# FT232B.net
KiCad netlist of a schematic drawn in Altium Designer
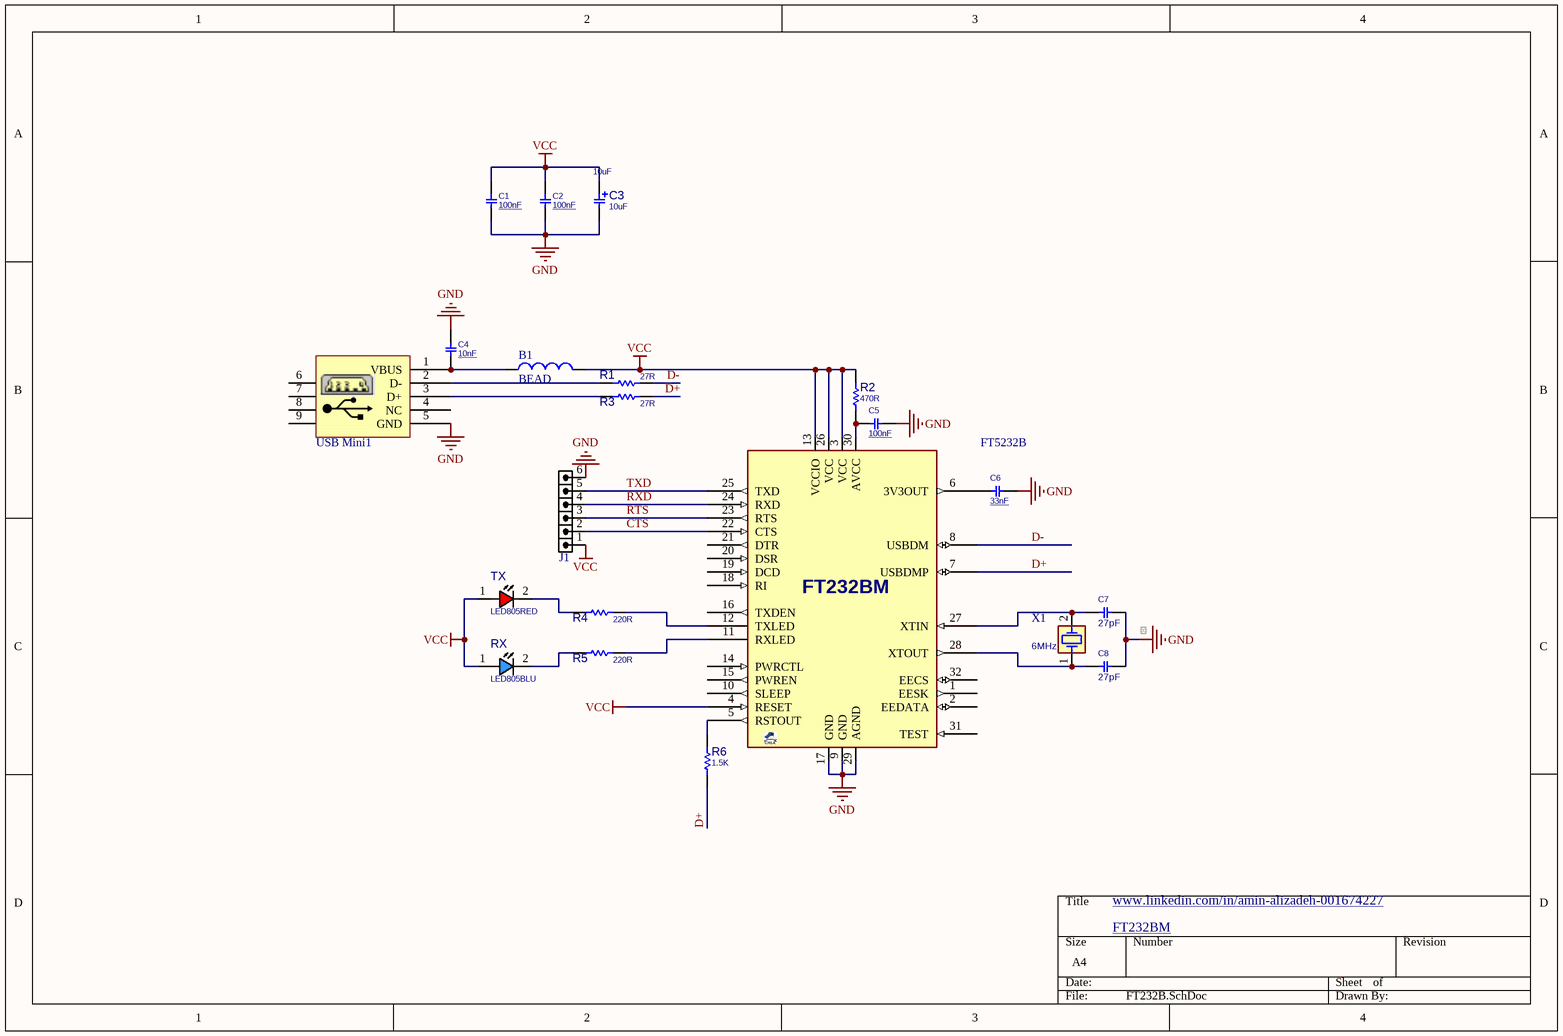
[diagram p0: FT232B.SchDoc]

(export (version "E")
  (design (tool "Eeschema 10.0.6"))
  (components
    (comp (ref "B1")
      (value "BEAD")
      (footprint "RES 0805 (2012X06L)")
      (description "FERIT BEAD SMD 1206")
      (libsource (lib "OMID_DXP_LIB93") (part "FERIT BEAD"))
    )
    (comp (ref "C1")
      (value "100nF")
      (footprint "C0805")
      (description "CAP, MLCC, -F, -V, MATERIAL, -%, 0201")
      (fields (field (name "MANF_P#") "MANF_PART#"))
      (libsource (lib "passive_smd") (part "CAP_SMD_MLCC_0805"))
    )
    (comp (ref "C2")
      (value "100nF")
      (footprint "C0805")
      (description "CAP, MLCC, -F, -V, MATERIAL, -%, 0201")
      (fields (field (name "MANF_P#") "MANF_PART#"))
      (libsource (lib "passive_smd") (part "CAP_SMD_MLCC_0805"))
    )
    (comp (ref "C3")
      (value "10uF")
      (footprint "C_EL_8")
      (description "CAP, THD, ELEC,")
      (fields
        (field (name "MANF_P#") "MANF_PART#")
        (field (name "MANF") "MANF")
        (field (name "ALTIUM_VALUE") "10uF")
      )
      (libsource (lib "passive_smd") (part "CAP_SMD_EL_8"))
    )
    (comp (ref "C4")
      (value "10nF")
      (footprint "C0805")
      (description "CAP, MLCC, -F, -V, MATERIAL, -%, 0201")
      (fields (field (name "MANF_P#") "MANF_PART#"))
      (libsource (lib "passive_smd") (part "CAP_SMD_MLCC_0805"))
    )
    (comp (ref "C5")
      (value "100nF")
      (footprint "C0805")
      (description "CAP, MLCC, -F, -V, MATERIAL, -%, 0201")
      (fields (field (name "MANF_P#") "MANF_PART#"))
      (libsource (lib "passive_smd") (part "CAP_SMD_MLCC_0805"))
    )
    (comp (ref "C6")
      (value "33nF")
      (footprint "C0805")
      (description "CAP, MLCC, -F, -V, MATERIAL, -%, 0201")
      (fields (field (name "MANF_P#") "MANF_PART#"))
      (libsource (lib "passive_smd") (part "CAP_SMD_MLCC_0805"))
    )
    (comp (ref "C7")
      (value "27pF")
      (footprint "C0805")
      (description "CAP, MLCC")
      (fields (field (name "MANF_P#") "MANF_PART#"))
      (libsource (lib "passive_smd") (part "CAP_SMD_MLCC_0805"))
    )
    (comp (ref "C8")
      (value "27pF")
      (footprint "C0805")
      (description "CAP, MLCC")
      (fields (field (name "MANF_P#") "MANF_PART#"))
      (libsource (lib "passive_smd") (part "CAP_SMD_MLCC_0805"))
    )
    (comp (ref "FT5232B")
      (value "FT232BM")
      (footprint "QFG80_32")
      (description "USB-UART")
      (fields (field (name "MANF") "FTDI"))
      (libsource (lib "usbic") (part "FT232BM_QFP32"))
    )
    (comp (ref "J1")
      (value "HDR1X6")
      (footprint "HDRR_M_1X6")
      (description "CONN, HEADER, Male, pitch: 2.54mm, 6POS")
      (libsource (lib "conn_header_2.54_ra") (part "HDRR_M_1X6"))
    )
    (comp (ref "R1")
      (value "27R")
      (footprint "R0805")
      (description "RESISTOR, SMD")
      (libsource (lib "passive_smd") (part "RES_SMD_0805"))
    )
    (comp (ref "R2")
      (value "470R")
      (footprint "R0805")
      (description "RESISTOR, SMD")
      (libsource (lib "passive_smd") (part "RES_SMD_0805"))
    )
    (comp (ref "R3")
      (value "27R")
      (footprint "R0805")
      (description "RESISTOR, SMD")
      (libsource (lib "passive_smd") (part "RES_SMD_0805"))
    )
    (comp (ref "R4")
      (value "220R")
      (footprint "R0805")
      (description "RESISTOR, SMD")
      (libsource (lib "passive_smd") (part "RES_SMD_0805"))
    )
    (comp (ref "R5")
      (value "220R")
      (footprint "R0805")
      (description "RESISTOR, SMD")
      (libsource (lib "passive_smd") (part "RES_SMD_0805"))
    )
    (comp (ref "R6")
      (value "1.5K")
      (footprint "R0805")
      (description "RESISTOR, SMD")
      (libsource (lib "passive_smd") (part "RES_SMD_0805"))
    )
    (comp (ref "RX")
      (value "LED805BLU")
      (footprint "LED0805BLU")
      (description "LED, SMD, 0805, BLUE")
      (fields (field (name "MANF") "MANF") (field (name "MANF_P#") "MANF_PART#"))
      (libsource (lib "led(diode)") (part "LED_SMD_0805_BLU"))
    )
    (comp (ref "TX")
      (value "LED805RED")
      (footprint "LED0805RED")
      (description "LED, SMD, 0805, RED")
      (fields (field (name "MANF") "MANF") (field (name "MANF_P#") "MANF_PART#"))
      (libsource (lib "led(diode)") (part "LED_SMD_0805_RED"))
    )
    (comp (ref "USB Mini1")
      (value "USB_Mini")
      (footprint "USB_Mini.2")
      (description "USB Mini")
      (fields (field (name "PUBLISHER") "Altium Limited"))
      (libsource (lib "A.Mohebbi") (part "USB_Mini"))
    )
    (comp (ref "X1")
      (value "6MHz")
      (footprint "XTL_2_11X5")
      (description "Crystal MOST POPULAR ABL HC49 PACKAGE")
      (fields (field (name "MANF") "ABRACON") (field (name "MANF_P#") "ABLS-8.000MHZ-B4-T"))
      (libsource (lib "crystal") (part "XTL_2_HC49_8MHz_SMD"))
    )
  )
  (nets
    (net (code "1") (name "/CTS") (class "Default")
      (node (ref "FT5232B") (pin "22") (pinfunction "CTS_22") (pintype "input"))
      (node (ref "J1") (pin "2") (pinfunction "2_2") (pintype "passive"))
    )
    (net (code "2") (name "/D+") (class "Default")
      (node (ref "FT5232B") (pin "7") (pinfunction "USBDMP_7") (pintype "bidirectional"))
      (node (ref "R3") (pin "1") (pinfunction "1_1") (pintype "passive"))
      (node (ref "R6") (pin "2") (pinfunction "2_2") (pintype "passive"))
    )
    (net (code "3") (name "/D-") (class "Default")
      (node (ref "FT5232B") (pin "8") (pinfunction "USBDM_8") (pintype "bidirectional"))
      (node (ref "R1") (pin "1") (pinfunction "1_1") (pintype "passive"))
    )
    (net (code "4") (name "/RTS") (class "Default")
      (node (ref "FT5232B") (pin "23") (pinfunction "RTS_23") (pintype "output"))
      (node (ref "J1") (pin "3") (pinfunction "3_3") (pintype "passive"))
    )
    (net (code "5") (name "/RXD") (class "Default")
      (node (ref "FT5232B") (pin "24") (pinfunction "RXD_24") (pintype "input"))
      (node (ref "J1") (pin "4") (pinfunction "4_4") (pintype "passive"))
    )
    (net (code "6") (name "/TXD") (class "Default")
      (node (ref "FT5232B") (pin "25") (pinfunction "TXD_25") (pintype "output"))
      (node (ref "J1") (pin "5") (pinfunction "5_5") (pintype "passive"))
    )
    (net (code "7") (name "GND") (class "Default")
      (node (ref "C1") (pin "2") (pinfunction "2_2") (pintype "passive"))
      (node (ref "C2") (pin "2") (pinfunction "2_2") (pintype "passive"))
      (node (ref "C3") (pin "2") (pinfunction "2_2") (pintype "passive"))
      (node (ref "C4") (pin "1") (pinfunction "1_1") (pintype "passive"))
      (node (ref "C5") (pin "1") (pinfunction "1_1") (pintype "passive"))
      (node (ref "C6") (pin "2") (pinfunction "2_2") (pintype "passive"))
      (node (ref "C7") (pin "1") (pinfunction "1_1") (pintype "passive"))
      (node (ref "C8") (pin "1") (pinfunction "1_1") (pintype "passive"))
      (node (ref "FT5232B") (pin "17") (pinfunction "GND_17") (pintype "power_in"))
      (node (ref "FT5232B") (pin "29") (pinfunction "AGND_29") (pintype "power_in"))
      (node (ref "FT5232B") (pin "9") (pinfunction "GND_9") (pintype "power_in"))
      (node (ref "J1") (pin "6") (pinfunction "6_6") (pintype "passive"))
      (node (ref "USB Mini1") (pin "5") (pinfunction "GND_5") (pintype "power_in"))
    )
    (net (code "8") (name "Net-(FT5232B-3V3OUT)") (class "Default")
      (node (ref "C6") (pin "1") (pinfunction "1_1") (pintype "passive"))
      (node (ref "FT5232B") (pin "6") (pinfunction "3V3OUT_6") (pintype "output"))
    )
    (net (code "9") (name "Net-(FT5232B-AVCC)") (class "Default")
      (node (ref "C5") (pin "2") (pinfunction "2_2") (pintype "passive"))
      (node (ref "FT5232B") (pin "30") (pinfunction "AVCC_30") (pintype "power_in"))
      (node (ref "R2") (pin "1") (pinfunction "1_1") (pintype "passive"))
    )
    (net (code "10") (name "Net-(FT5232B-RSTOUT)") (class "Default")
      (node (ref "FT5232B") (pin "5") (pinfunction "RSTOUT_5") (pintype "output"))
      (node (ref "R6") (pin "1") (pinfunction "1_1") (pintype "passive"))
    )
    (net (code "11") (name "Net-(FT5232B-RXLED)") (class "Default")
      (node (ref "FT5232B") (pin "11") (pinfunction "RXLED_11") (pintype "open_collector"))
      (node (ref "R5") (pin "1") (pinfunction "1_1") (pintype "passive"))
    )
    (net (code "12") (name "Net-(FT5232B-TXLED)") (class "Default")
      (node (ref "FT5232B") (pin "12") (pinfunction "TXLED_12") (pintype "open_collector"))
      (node (ref "R4") (pin "1") (pinfunction "1_1") (pintype "passive"))
    )
    (net (code "13") (name "Net-(FT5232B-XTIN)") (class "Default")
      (node (ref "C7") (pin "2") (pinfunction "2_2") (pintype "passive"))
      (node (ref "FT5232B") (pin "27") (pinfunction "XTIN_27") (pintype "input"))
      (node (ref "X1") (pin "2") (pinfunction "OSC2_2") (pintype "passive"))
    )
    (net (code "14") (name "Net-(FT5232B-XTOUT)") (class "Default")
      (node (ref "C8") (pin "2") (pinfunction "2_2") (pintype "passive"))
      (node (ref "FT5232B") (pin "28") (pinfunction "XTOUT_28") (pintype "output"))
      (node (ref "X1") (pin "1") (pinfunction "OSC1_1") (pintype "passive"))
    )
    (net (code "15") (name "Net-(RX-CATHODE)") (class "Default")
      (node (ref "R5") (pin "2") (pinfunction "2_2") (pintype "passive"))
      (node (ref "RX") (pin "2") (pinfunction "CATHODE_2") (pintype "passive"))
    )
    (net (code "16") (name "Net-(TX-CATHODE)") (class "Default")
      (node (ref "R4") (pin "2") (pinfunction "2_2") (pintype "passive"))
      (node (ref "TX") (pin "2") (pinfunction "CATHODE_2") (pintype "passive"))
    )
    (net (code "17") (name "Net-(USB Mini1-D+)") (class "Default")
      (node (ref "R3") (pin "2") (pinfunction "2_2") (pintype "passive"))
      (node (ref "USB Mini1") (pin "3") (pinfunction "D+_3") (pintype "passive"))
    )
    (net (code "18") (name "Net-(USB Mini1-D-)") (class "Default")
      (node (ref "R1") (pin "2") (pinfunction "2_2") (pintype "passive"))
      (node (ref "USB Mini1") (pin "2") (pinfunction "D-_2") (pintype "passive"))
    )
    (net (code "19") (name "Net-(USB Mini1-VBUS)") (class "Default")
      (node (ref "B1") (pin "1") (pinfunction "1_1") (pintype "passive"))
      (node (ref "C4") (pin "2") (pinfunction "2_2") (pintype "passive"))
      (node (ref "USB Mini1") (pin "1") (pinfunction "VBUS_1") (pintype "power_in"))
    )
    (net (code "20") (name "VCC") (class "Default")
      (node (ref "B1") (pin "2") (pinfunction "2_2") (pintype "passive"))
      (node (ref "C1") (pin "1") (pinfunction "1_1") (pintype "passive"))
      (node (ref "C2") (pin "1") (pinfunction "1_1") (pintype "passive"))
      (node (ref "C3") (pin "1") (pinfunction "1_1") (pintype "passive"))
      (node (ref "FT5232B") (pin "13") (pinfunction "VCCIO_13") (pintype "power_in"))
      (node (ref "FT5232B") (pin "26") (pinfunction "VCC_26") (pintype "power_in"))
      (node (ref "FT5232B") (pin "3") (pinfunction "VCC_3") (pintype "power_in"))
      (node (ref "FT5232B") (pin "4") (pinfunction "RESET_4") (pintype "input"))
      (node (ref "J1") (pin "1") (pinfunction "1_1") (pintype "passive"))
      (node (ref "R2") (pin "2") (pinfunction "2_2") (pintype "passive"))
      (node (ref "RX") (pin "1") (pinfunction "ANODE_1") (pintype "passive"))
      (node (ref "TX") (pin "1") (pinfunction "ANODE_1") (pintype "passive"))
    )
    (net (code "21") (name "unconnected-(FT5232B-DCD-Pad19)") (class "Default")
      (node (ref "FT5232B") (pin "19") (pinfunction "DCD_19") (pintype "input"))
    )
    (net (code "22") (name "unconnected-(FT5232B-DSR-Pad20)") (class "Default")
      (node (ref "FT5232B") (pin "20") (pinfunction "DSR_20") (pintype "input"))
    )
    (net (code "23") (name "unconnected-(FT5232B-DTR-Pad21)") (class "Default")
      (node (ref "FT5232B") (pin "21") (pinfunction "DTR_21") (pintype "output"))
    )
    (net (code "24") (name "unconnected-(FT5232B-EECS-Pad32)") (class "Default")
      (node (ref "FT5232B") (pin "32") (pinfunction "EECS_32") (pintype "bidirectional"))
    )
    (net (code "25") (name "unconnected-(FT5232B-EEDATA-Pad2)") (class "Default")
      (node (ref "FT5232B") (pin "2") (pinfunction "EEDATA_2") (pintype "bidirectional"))
    )
    (net (code "26") (name "unconnected-(FT5232B-EESK-Pad1)") (class "Default")
      (node (ref "FT5232B") (pin "1") (pinfunction "EESK_1") (pintype "output"))
    )
    (net (code "27") (name "unconnected-(FT5232B-PWRCTL-Pad14)") (class "Default")
      (node (ref "FT5232B") (pin "14") (pinfunction "PWRCTL_14") (pintype "input"))
    )
    (net (code "28") (name "unconnected-(FT5232B-PWREN-Pad15)") (class "Default")
      (node (ref "FT5232B") (pin "15") (pinfunction "PWREN_15") (pintype "output"))
    )
    (net (code "29") (name "unconnected-(FT5232B-RI-Pad18)") (class "Default")
      (node (ref "FT5232B") (pin "18") (pinfunction "RI_18") (pintype "input"))
    )
    (net (code "30") (name "unconnected-(FT5232B-SLEEP-Pad10)") (class "Default")
      (node (ref "FT5232B") (pin "10") (pinfunction "SLEEP_10") (pintype "output"))
    )
    (net (code "31") (name "unconnected-(FT5232B-TEST-Pad31)") (class "Default")
      (node (ref "FT5232B") (pin "31") (pinfunction "TEST_31") (pintype "input"))
    )
    (net (code "32") (name "unconnected-(FT5232B-TXDEN-Pad16)") (class "Default")
      (node (ref "FT5232B") (pin "16") (pinfunction "TXDEN_16") (pintype "output"))
    )
    (net (code "33") (name "unconnected-(USB Mini1-NC-Pad4)") (class "Default")
      (node (ref "USB Mini1") (pin "4") (pinfunction "NC_4") (pintype "power_in"))
    )
    (net (code "34") (name "unconnected-(USB Mini1-Pad6)") (class "Default")
      (node (ref "USB Mini1") (pin "6") (pinfunction "6_6") (pintype "passive"))
    )
    (net (code "35") (name "unconnected-(USB Mini1-Pad7)") (class "Default")
      (node (ref "USB Mini1") (pin "7") (pinfunction "7_7") (pintype "passive"))
    )
    (net (code "36") (name "unconnected-(USB Mini1-Pad8)") (class "Default")
      (node (ref "USB Mini1") (pin "8") (pinfunction "8_8") (pintype "passive"))
    )
    (net (code "37") (name "unconnected-(USB Mini1-Pad9)") (class "Default")
      (node (ref "USB Mini1") (pin "9") (pinfunction "9_9") (pintype "passive"))
    )
  )
)
